# Even.net
KiCad netlist of a schematic drawn in Altium Designer
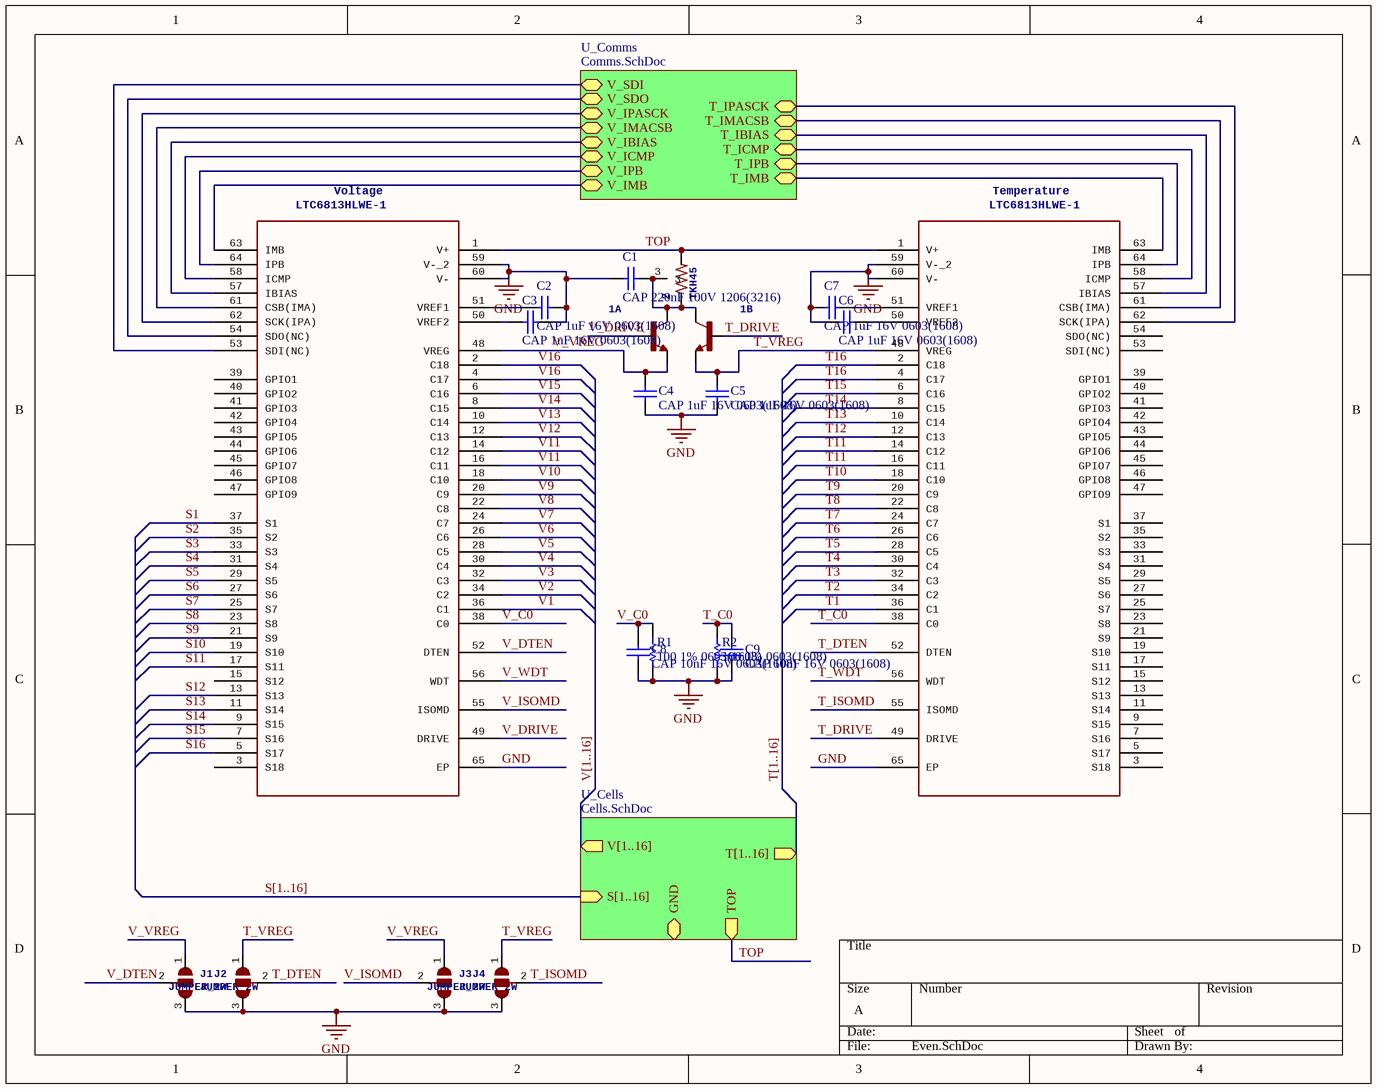
[diagram p0: Even.SchDoc]

(export (version "E")
  (design (tool "Eeschema 10.0.6"))
  (components
    (comp (ref "1")
      (value "PHPT610030NK")
      (footprint "LFPAK56D")
      (fields (field (name "LIBRARYNAME") "IFE_Transistors"))
      (libsource (lib "IFE_Transistors") (part "PHPT610030NK"))
    )
    (comp (ref "2")
      (value "TKH45")
      (footprint "TO252-TKH-45")
      (fields (field (name "LIBRARYNAME") "IFE_Resistors"))
      (libsource (lib "IFE_Resistors") (part "TKH45"))
    )
    (comp (ref "C1")
      (value "CAP 220nF 100V 1206(3216)")
      (footprint "CAPC1206(3216)190_L")
      (description "CAP 220nF 100V ±10% 1206 (3216 Metric) Thickness 1.9mm SMD")
      (fields (field (name "TOLERANCE") "Â±10%"))
      (libsource (lib "Altium Content Vault") (part "CAP"))
    )
    (comp (ref "C2")
      (value "CAP 1uF 16V 0603(1608)")
      (footprint "CAPC0603(1608)100_N")
      (description "CAP 1uF 16V ±5% 0603 (1608 Metric) Thickness 1mm SMD")
      (fields (field (name "TOLERANCE") "Â±5%"))
      (libsource (lib "Altium Content Vault") (part "CAP"))
    )
    (comp (ref "C3")
      (value "CAP 1uF 16V 0603(1608)")
      (footprint "CAPC0603(1608)100_N")
      (description "CAP 1uF 16V ±5% 0603 (1608 Metric) Thickness 1mm SMD")
      (fields (field (name "TOLERANCE") "Â±5%"))
      (libsource (lib "Altium Content Vault") (part "CAP"))
    )
    (comp (ref "C4")
      (value "CAP 1uF 16V 0603(1608)")
      (footprint "CAPC0603(1608)100_N")
      (description "CAP 1uF 16V ±5% 0603 (1608 Metric) Thickness 1mm SMD")
      (fields (field (name "TOLERANCE") "Â±5%"))
      (libsource (lib "Altium Content Vault") (part "CAP"))
    )
    (comp (ref "C5")
      (value "CAP 1uF 16V 0603(1608)")
      (footprint "CAPC0603(1608)100_N")
      (description "CAP 1uF 16V ±5% 0603 (1608 Metric) Thickness 1mm SMD")
      (fields (field (name "TOLERANCE") "Â±5%"))
      (libsource (lib "Altium Content Vault") (part "CAP"))
    )
    (comp (ref "C6")
      (value "CAP 1uF 16V 0603(1608)")
      (footprint "CAPC0603(1608)100_N")
      (description "CAP 1uF 16V ±5% 0603 (1608 Metric) Thickness 1mm SMD")
      (fields (field (name "TOLERANCE") "Â±5%"))
      (libsource (lib "Altium Content Vault") (part "CAP"))
    )
    (comp (ref "C7")
      (value "CAP 1uF 16V 0603(1608)")
      (footprint "CAPC0603(1608)100_N")
      (description "CAP 1uF 16V ±5% 0603 (1608 Metric) Thickness 1mm SMD")
      (fields (field (name "TOLERANCE") "Â±5%"))
      (libsource (lib "Altium Content Vault") (part "CAP"))
    )
    (comp (ref "C8")
      (value "CAP 10nF 16V 0603(1608)")
      (footprint "CAPC0603(1608)100_L")
      (description "CAP 10nF 16V ±1% 0603 (1608 Metric) Thickness 1mm SMD")
      (fields (field (name "TOLERANCE") "Â±1%"))
      (libsource (lib "Altium Content Vault") (part "CAP"))
    )
    (comp (ref "C9")
      (value "CAP 10nF 16V 0603(1608)")
      (footprint "CAPC0603(1608)100_L")
      (description "CAP 10nF 16V ±1% 0603 (1608 Metric) Thickness 1mm SMD")
      (fields (field (name "TOLERANCE") "Â±1%"))
      (libsource (lib "Altium Content Vault") (part "CAP"))
    )
    (comp (ref "J1")
      (value "JUMPER_2W")
      (footprint "SJ_2")
      (fields (field (name "LIBRARYNAME") "IFE_Jumpers"))
      (libsource (lib "") (part "JUMPER_2W_1"))
    )
    (comp (ref "J2")
      (value "JUMPER_2W")
      (footprint "SJ_2")
      (fields (field (name "LIBRARYNAME") "IFE_Jumpers"))
      (libsource (lib "IFE_Jumpers") (part "JUMPER_2W"))
    )
    (comp (ref "J3")
      (value "JUMPER_2W")
      (footprint "SJ_2")
      (fields (field (name "LIBRARYNAME") "IFE_Jumpers"))
      (libsource (lib "") (part "JUMPER_2W_1"))
    )
    (comp (ref "J4")
      (value "JUMPER_2W")
      (footprint "SJ_2")
      (fields (field (name "LIBRARYNAME") "IFE_Jumpers"))
      (libsource (lib "IFE_Jumpers") (part "JUMPER_2W"))
    )
    (comp (ref "R1")
      (value "100 1% 0603(1608)")
      (footprint "RESC0603(1608)_L")
      (description "2R94 0.1W 1% 0603 (1608 Metric)  SMD")
      (fields (field (name "POWER") "0.1 W") (field (name "TOLERANCE") "1 %"))
      (libsource (lib "Altium Content Vault") (part "RES"))
    )
    (comp (ref "R2")
      (value "100 1% 0603(1608)")
      (footprint "RESC0603(1608)_L")
      (description "2R94 0.1W 1% 0603 (1608 Metric)  SMD")
      (fields (field (name "POWER") "0.1 W") (field (name "TOLERANCE") "1 %"))
      (libsource (lib "Altium Content Vault") (part "RES"))
    )
    (comp (ref "Temperature")
      (value "LTC6813HLWE-1")
      (footprint "LQFP64_LWE_A")
      (fields (field (name "LIBRARYNAME") "LTC6813_Official"))
      (libsource (lib "LTC6813_Official") (part "LTC6813HLWE-1"))
    )
    (comp (ref "Voltage")
      (value "LTC6813HLWE-1")
      (footprint "LQFP64_LWE_A")
      (fields (field (name "LIBRARYNAME") "LTC6813_Official"))
      (libsource (lib "LTC6813_Official") (part "LTC6813HLWE-1"))
    )
  )
  (nets
    (net (code "2") (name "/S1") (class "Default")
      (node (ref "Voltage") (pin "37") (pinfunction "S1_37") (pintype "passive"))
    )
    (net (code "3") (name "/S2") (class "Default")
      (node (ref "Voltage") (pin "35") (pinfunction "S2_35") (pintype "passive"))
    )
    (net (code "4") (name "/S3") (class "Default")
      (node (ref "Voltage") (pin "33") (pinfunction "S3_33") (pintype "passive"))
    )
    (net (code "5") (name "/S4") (class "Default")
      (node (ref "Voltage") (pin "31") (pinfunction "S4_31") (pintype "passive"))
    )
    (net (code "6") (name "/S5") (class "Default")
      (node (ref "Voltage") (pin "29") (pinfunction "S5_29") (pintype "passive"))
    )
    (net (code "7") (name "/S6") (class "Default")
      (node (ref "Voltage") (pin "27") (pinfunction "S6_27") (pintype "passive"))
    )
    (net (code "8") (name "/S7") (class "Default")
      (node (ref "Voltage") (pin "25") (pinfunction "S7_25") (pintype "passive"))
    )
    (net (code "9") (name "/S8") (class "Default")
      (node (ref "Voltage") (pin "23") (pinfunction "S8_23") (pintype "passive"))
    )
    (net (code "10") (name "/S9") (class "Default")
      (node (ref "Voltage") (pin "21") (pinfunction "S9_21") (pintype "passive"))
    )
    (net (code "11") (name "/S10") (class "Default")
      (node (ref "Voltage") (pin "19") (pinfunction "S10_19") (pintype "passive"))
    )
    (net (code "12") (name "/S11") (class "Default")
      (node (ref "Voltage") (pin "17") (pinfunction "S11_17") (pintype "passive"))
    )
    (net (code "13") (name "/S12") (class "Default")
      (node (ref "Voltage") (pin "13") (pinfunction "S13_13") (pintype "passive"))
    )
    (net (code "14") (name "/S13") (class "Default")
      (node (ref "Voltage") (pin "11") (pinfunction "S14_11") (pintype "passive"))
    )
    (net (code "15") (name "/S14") (class "Default")
      (node (ref "Voltage") (pin "9") (pinfunction "S15_9") (pintype "passive"))
    )
    (net (code "16") (name "/S15") (class "Default")
      (node (ref "Voltage") (pin "7") (pinfunction "S16_7") (pintype "passive"))
    )
    (net (code "17") (name "/S16") (class "Default")
      (node (ref "Voltage") (pin "5") (pinfunction "S17_5") (pintype "passive"))
    )
    (net (code "19") (name "/T1") (class "Default")
      (node (ref "Temperature") (pin "36") (pinfunction "C1_36") (pintype "passive"))
    )
    (net (code "20") (name "/T2") (class "Default")
      (node (ref "Temperature") (pin "34") (pinfunction "C2_34") (pintype "passive"))
    )
    (net (code "21") (name "/T3") (class "Default")
      (node (ref "Temperature") (pin "32") (pinfunction "C3_32") (pintype "passive"))
    )
    (net (code "22") (name "/T4") (class "Default")
      (node (ref "Temperature") (pin "30") (pinfunction "C4_30") (pintype "passive"))
    )
    (net (code "23") (name "/T5") (class "Default")
      (node (ref "Temperature") (pin "28") (pinfunction "C5_28") (pintype "passive"))
    )
    (net (code "24") (name "/T6") (class "Default")
      (node (ref "Temperature") (pin "26") (pinfunction "C6_26") (pintype "passive"))
    )
    (net (code "25") (name "/T7") (class "Default")
      (node (ref "Temperature") (pin "24") (pinfunction "C7_24") (pintype "passive"))
    )
    (net (code "26") (name "/T8") (class "Default")
      (node (ref "Temperature") (pin "22") (pinfunction "C8_22") (pintype "passive"))
    )
    (net (code "27") (name "/T9") (class "Default")
      (node (ref "Temperature") (pin "20") (pinfunction "C9_20") (pintype "passive"))
    )
    (net (code "28") (name "/T10") (class "Default")
      (node (ref "Temperature") (pin "18") (pinfunction "C10_18") (pintype "passive"))
    )
    (net (code "29") (name "/T11") (class "Default")
      (node (ref "Temperature") (pin "14") (pinfunction "C12_14") (pintype "passive"))
      (node (ref "Temperature") (pin "16") (pinfunction "C11_16") (pintype "passive"))
    )
    (net (code "30") (name "/T12") (class "Default")
      (node (ref "Temperature") (pin "12") (pinfunction "C13_12") (pintype "passive"))
    )
    (net (code "31") (name "/T13") (class "Default")
      (node (ref "Temperature") (pin "10") (pinfunction "C14_10") (pintype "passive"))
    )
    (net (code "32") (name "/T14") (class "Default")
      (node (ref "Temperature") (pin "8") (pinfunction "C15_8") (pintype "passive"))
    )
    (net (code "33") (name "/T15") (class "Default")
      (node (ref "Temperature") (pin "6") (pinfunction "C16_6") (pintype "passive"))
    )
    (net (code "34") (name "/T16") (class "Default")
      (node (ref "Temperature") (pin "2") (pinfunction "C18_2") (pintype "passive"))
      (node (ref "Temperature") (pin "4") (pinfunction "C17_4") (pintype "passive"))
    )
    (net (code "35") (name "/TOP") (class "Default")
      (node (ref "2") (pin "2") (pinfunction "2_2") (pintype "passive"))
      (node (ref "Temperature") (pin "1") (pinfunction "V+_1") (pintype "passive"))
      (node (ref "Voltage") (pin "1") (pinfunction "V+_1") (pintype "passive"))
    )
    (net (code "37") (name "/T_C0") (class "Default")
      (node (ref "C9") (pin "2") (pinfunction "2_2") (pintype "passive"))
      (node (ref "R2") (pin "1") (pinfunction "1_1") (pintype "passive"))
      (node (ref "Temperature") (pin "38") (pinfunction "C0_38") (pintype "passive"))
    )
    (net (code "38") (name "/T_DRIVE") (class "Default")
      (node (ref "1") (pin "B2") (pinfunction "B_B2") (pintype "passive"))
      (node (ref "Temperature") (pin "49") (pinfunction "DRIVE_49") (pintype "passive"))
    )
    (net (code "39") (name "/T_DTEN") (class "Default")
      (node (ref "J2") (pin "2") (pinfunction "2_2") (pintype "passive"))
      (node (ref "Temperature") (pin "52") (pinfunction "DTEN_52") (pintype "passive"))
    )
    (net (code "40") (name "/T_IBIAS") (class "Default")
      (node (ref "Temperature") (pin "57") (pinfunction "IBIAS_57") (pintype "passive"))
    )
    (net (code "41") (name "/T_ICMP") (class "Default")
      (node (ref "Temperature") (pin "58") (pinfunction "ICMP_58") (pintype "passive"))
    )
    (net (code "42") (name "/T_IMACSB") (class "Default")
      (node (ref "Temperature") (pin "61") (pinfunction "CSB(IMA)_61") (pintype "passive"))
    )
    (net (code "43") (name "/T_IMB") (class "Default")
      (node (ref "Temperature") (pin "63") (pinfunction "IMB_63") (pintype "passive"))
    )
    (net (code "44") (name "/T_IPASCK") (class "Default")
      (node (ref "Temperature") (pin "62") (pinfunction "SCK(IPA)_62") (pintype "passive"))
    )
    (net (code "45") (name "/T_IPB") (class "Default")
      (node (ref "Temperature") (pin "64") (pinfunction "IPB_64") (pintype "passive"))
    )
    (net (code "46") (name "/T_ISOMD") (class "Default")
      (node (ref "J4") (pin "2") (pinfunction "2_2") (pintype "passive"))
      (node (ref "Temperature") (pin "55") (pinfunction "ISOMD_55") (pintype "passive"))
    )
    (net (code "47") (name "/T_VREG") (class "Default")
      (node (ref "1") (pin "E2") (pinfunction "E_E2") (pintype "passive"))
      (node (ref "C5") (pin "2") (pinfunction "2_2") (pintype "passive"))
      (node (ref "J2") (pin "1") (pinfunction "1_1") (pintype "passive"))
      (node (ref "J4") (pin "1") (pinfunction "1_1") (pintype "passive"))
      (node (ref "Temperature") (pin "48") (pinfunction "VREG_48") (pintype "passive"))
    )
    (net (code "48") (name "/T_WDT") (class "Default")
      (node (ref "Temperature") (pin "56") (pinfunction "WDT_56") (pintype "passive"))
    )
    (net (code "49") (name "/V1") (class "Default")
      (node (ref "Voltage") (pin "36") (pinfunction "C1_36") (pintype "passive"))
    )
    (net (code "50") (name "/V2") (class "Default")
      (node (ref "Voltage") (pin "34") (pinfunction "C2_34") (pintype "passive"))
    )
    (net (code "51") (name "/V3") (class "Default")
      (node (ref "Voltage") (pin "32") (pinfunction "C3_32") (pintype "passive"))
    )
    (net (code "52") (name "/V4") (class "Default")
      (node (ref "Voltage") (pin "30") (pinfunction "C4_30") (pintype "passive"))
    )
    (net (code "53") (name "/V5") (class "Default")
      (node (ref "Voltage") (pin "28") (pinfunction "C5_28") (pintype "passive"))
    )
    (net (code "54") (name "/V6") (class "Default")
      (node (ref "Voltage") (pin "26") (pinfunction "C6_26") (pintype "passive"))
    )
    (net (code "55") (name "/V7") (class "Default")
      (node (ref "Voltage") (pin "24") (pinfunction "C7_24") (pintype "passive"))
    )
    (net (code "56") (name "/V8") (class "Default")
      (node (ref "Voltage") (pin "22") (pinfunction "C8_22") (pintype "passive"))
    )
    (net (code "57") (name "/V9") (class "Default")
      (node (ref "Voltage") (pin "20") (pinfunction "C9_20") (pintype "passive"))
    )
    (net (code "58") (name "/V10") (class "Default")
      (node (ref "Voltage") (pin "18") (pinfunction "C10_18") (pintype "passive"))
    )
    (net (code "59") (name "/V11") (class "Default")
      (node (ref "Voltage") (pin "14") (pinfunction "C12_14") (pintype "passive"))
      (node (ref "Voltage") (pin "16") (pinfunction "C11_16") (pintype "passive"))
    )
    (net (code "60") (name "/V12") (class "Default")
      (node (ref "Voltage") (pin "12") (pinfunction "C13_12") (pintype "passive"))
    )
    (net (code "61") (name "/V13") (class "Default")
      (node (ref "Voltage") (pin "10") (pinfunction "C14_10") (pintype "passive"))
    )
    (net (code "62") (name "/V14") (class "Default")
      (node (ref "Voltage") (pin "8") (pinfunction "C15_8") (pintype "passive"))
    )
    (net (code "63") (name "/V15") (class "Default")
      (node (ref "Voltage") (pin "6") (pinfunction "C16_6") (pintype "passive"))
    )
    (net (code "64") (name "/V16") (class "Default")
      (node (ref "Voltage") (pin "2") (pinfunction "C18_2") (pintype "passive"))
      (node (ref "Voltage") (pin "4") (pinfunction "C17_4") (pintype "passive"))
    )
    (net (code "66") (name "/V_C0") (class "Default")
      (node (ref "C8") (pin "1") (pinfunction "1_1") (pintype "passive"))
      (node (ref "R1") (pin "2") (pinfunction "2_2") (pintype "passive"))
      (node (ref "Voltage") (pin "38") (pinfunction "C0_38") (pintype "passive"))
    )
    (net (code "67") (name "/V_DRIVE") (class "Default")
      (node (ref "1") (pin "B1") (pinfunction "B_B1") (pintype "passive"))
      (node (ref "Voltage") (pin "49") (pinfunction "DRIVE_49") (pintype "passive"))
    )
    (net (code "68") (name "/V_DTEN") (class "Default")
      (node (ref "J1") (pin "2") (pinfunction "2_2") (pintype "passive"))
      (node (ref "Voltage") (pin "52") (pinfunction "DTEN_52") (pintype "passive"))
    )
    (net (code "69") (name "/V_IBIAS") (class "Default")
      (node (ref "Voltage") (pin "57") (pinfunction "IBIAS_57") (pintype "passive"))
    )
    (net (code "70") (name "/V_ICMP") (class "Default")
      (node (ref "Voltage") (pin "58") (pinfunction "ICMP_58") (pintype "passive"))
    )
    (net (code "71") (name "/V_IMACSB") (class "Default")
      (node (ref "Voltage") (pin "61") (pinfunction "CSB(IMA)_61") (pintype "passive"))
    )
    (net (code "72") (name "/V_IMB") (class "Default")
      (node (ref "Voltage") (pin "63") (pinfunction "IMB_63") (pintype "passive"))
    )
    (net (code "73") (name "/V_IPASCK") (class "Default")
      (node (ref "Voltage") (pin "62") (pinfunction "SCK(IPA)_62") (pintype "passive"))
    )
    (net (code "74") (name "/V_IPB") (class "Default")
      (node (ref "Voltage") (pin "64") (pinfunction "IPB_64") (pintype "passive"))
    )
    (net (code "75") (name "/V_ISOMD") (class "Default")
      (node (ref "J3") (pin "2") (pinfunction "2_2") (pintype "passive"))
      (node (ref "Voltage") (pin "55") (pinfunction "ISOMD_55") (pintype "passive"))
    )
    (net (code "76") (name "/V_SDI") (class "Default")
      (node (ref "Voltage") (pin "53") (pinfunction "SDI(NC)_53") (pintype "passive"))
    )
    (net (code "77") (name "/V_SDO") (class "Default")
      (node (ref "Voltage") (pin "54") (pinfunction "SDO(NC)_54") (pintype "passive"))
    )
    (net (code "78") (name "/V_VREG") (class "Default")
      (node (ref "1") (pin "E1") (pinfunction "E_E1") (pintype "passive"))
      (node (ref "C4") (pin "2") (pinfunction "2_2") (pintype "passive"))
      (node (ref "J1") (pin "1") (pinfunction "1_1") (pintype "passive"))
      (node (ref "J3") (pin "1") (pinfunction "1_1") (pintype "passive"))
      (node (ref "Voltage") (pin "48") (pinfunction "VREG_48") (pintype "passive"))
    )
    (net (code "79") (name "/V_WDT") (class "Default")
      (node (ref "Voltage") (pin "56") (pinfunction "WDT_56") (pintype "passive"))
    )
    (net (code "80") (name "GND") (class "Default")
      (node (ref "C1") (pin "1") (pinfunction "1_1") (pintype "passive"))
      (node (ref "C2") (pin "2") (pinfunction "2_2") (pintype "passive"))
      (node (ref "C3") (pin "2") (pinfunction "2_2") (pintype "passive"))
      (node (ref "C4") (pin "1") (pinfunction "1_1") (pintype "passive"))
      (node (ref "C5") (pin "1") (pinfunction "1_1") (pintype "passive"))
      (node (ref "C6") (pin "1") (pinfunction "1_1") (pintype "passive"))
      (node (ref "C7") (pin "1") (pinfunction "1_1") (pintype "passive"))
      (node (ref "C8") (pin "2") (pinfunction "2_2") (pintype "passive"))
      (node (ref "C9") (pin "1") (pinfunction "1_1") (pintype "passive"))
      (node (ref "J1") (pin "3") (pinfunction "3_3") (pintype "passive"))
      (node (ref "J2") (pin "3") (pinfunction "3_3") (pintype "passive"))
      (node (ref "J3") (pin "3") (pinfunction "3_3") (pintype "passive"))
      (node (ref "J4") (pin "3") (pinfunction "3_3") (pintype "passive"))
      (node (ref "R1") (pin "1") (pinfunction "1_1") (pintype "passive"))
      (node (ref "R2") (pin "2") (pinfunction "2_2") (pintype "passive"))
      (node (ref "Temperature") (pin "59") (pinfunction "V-_2_59") (pintype "passive"))
      (node (ref "Temperature") (pin "60") (pinfunction "V-_60") (pintype "passive"))
      (node (ref "Temperature") (pin "65") (pinfunction "EP_65") (pintype "passive"))
      (node (ref "Voltage") (pin "59") (pinfunction "V-_2_59") (pintype "passive"))
      (node (ref "Voltage") (pin "60") (pinfunction "V-_60") (pintype "passive"))
      (node (ref "Voltage") (pin "65") (pinfunction "EP_65") (pintype "passive"))
    )
    (net (code "81") (name "Net-(1A-C)") (class "Default")
      (node (ref "1") (pin "C1") (pinfunction "C_C1") (pintype "passive"))
      (node (ref "1") (pin "C2") (pinfunction "C_C2") (pintype "passive"))
      (node (ref "2") (pin "1") (pinfunction "1_1") (pintype "passive"))
      (node (ref "2") (pin "3") (pinfunction "3_3") (pintype "passive"))
      (node (ref "C1") (pin "2") (pinfunction "2_2") (pintype "passive"))
    )
    (net (code "82") (name "Net-(Temperature-VREF1)") (class "Default")
      (node (ref "C7") (pin "2") (pinfunction "2_2") (pintype "passive"))
      (node (ref "Temperature") (pin "51") (pinfunction "VREF1_51") (pintype "passive"))
    )
    (net (code "83") (name "Net-(Temperature-VREF2)") (class "Default")
      (node (ref "C6") (pin "2") (pinfunction "2_2") (pintype "passive"))
      (node (ref "Temperature") (pin "50") (pinfunction "VREF2_50") (pintype "passive"))
    )
    (net (code "84") (name "Net-(Voltage-VREF1)") (class "Default")
      (node (ref "C2") (pin "1") (pinfunction "1_1") (pintype "passive"))
      (node (ref "Voltage") (pin "51") (pinfunction "VREF1_51") (pintype "passive"))
    )
    (net (code "85") (name "Net-(Voltage-VREF2)") (class "Default")
      (node (ref "C3") (pin "1") (pinfunction "1_1") (pintype "passive"))
      (node (ref "Voltage") (pin "50") (pinfunction "VREF2_50") (pintype "passive"))
    )
    (net (code "86") (name "unconnected-(Temperature-GPIO1-Pad39)") (class "Default")
      (node (ref "Temperature") (pin "39") (pinfunction "GPIO1_39") (pintype "passive"))
    )
    (net (code "87") (name "unconnected-(Temperature-GPIO2-Pad40)") (class "Default")
      (node (ref "Temperature") (pin "40") (pinfunction "GPIO2_40") (pintype "passive"))
    )
    (net (code "88") (name "unconnected-(Temperature-GPIO3-Pad41)") (class "Default")
      (node (ref "Temperature") (pin "41") (pinfunction "GPIO3_41") (pintype "passive"))
    )
    (net (code "89") (name "unconnected-(Temperature-GPIO4-Pad42)") (class "Default")
      (node (ref "Temperature") (pin "42") (pinfunction "GPIO4_42") (pintype "passive"))
    )
    (net (code "90") (name "unconnected-(Temperature-GPIO5-Pad43)") (class "Default")
      (node (ref "Temperature") (pin "43") (pinfunction "GPIO5_43") (pintype "passive"))
    )
    (net (code "91") (name "unconnected-(Temperature-GPIO6-Pad44)") (class "Default")
      (node (ref "Temperature") (pin "44") (pinfunction "GPIO6_44") (pintype "passive"))
    )
    (net (code "92") (name "unconnected-(Temperature-GPIO7-Pad45)") (class "Default")
      (node (ref "Temperature") (pin "45") (pinfunction "GPIO7_45") (pintype "passive"))
    )
    (net (code "93") (name "unconnected-(Temperature-GPIO8-Pad46)") (class "Default")
      (node (ref "Temperature") (pin "46") (pinfunction "GPIO8_46") (pintype "passive"))
    )
    (net (code "94") (name "unconnected-(Temperature-GPIO9-Pad47)") (class "Default")
      (node (ref "Temperature") (pin "47") (pinfunction "GPIO9_47") (pintype "passive"))
    )
    (net (code "95") (name "unconnected-(Temperature-S1-Pad37)") (class "Default")
      (node (ref "Temperature") (pin "37") (pinfunction "S1_37") (pintype "passive"))
    )
    (net (code "96") (name "unconnected-(Temperature-S2-Pad35)") (class "Default")
      (node (ref "Temperature") (pin "35") (pinfunction "S2_35") (pintype "passive"))
    )
    (net (code "97") (name "unconnected-(Temperature-S3-Pad33)") (class "Default")
      (node (ref "Temperature") (pin "33") (pinfunction "S3_33") (pintype "passive"))
    )
    (net (code "98") (name "unconnected-(Temperature-S4-Pad31)") (class "Default")
      (node (ref "Temperature") (pin "31") (pinfunction "S4_31") (pintype "passive"))
    )
    (net (code "99") (name "unconnected-(Temperature-S5-Pad29)") (class "Default")
      (node (ref "Temperature") (pin "29") (pinfunction "S5_29") (pintype "passive"))
    )
    (net (code "100") (name "unconnected-(Temperature-S6-Pad27)") (class "Default")
      (node (ref "Temperature") (pin "27") (pinfunction "S6_27") (pintype "passive"))
    )
    (net (code "101") (name "unconnected-(Temperature-S7-Pad25)") (class "Default")
      (node (ref "Temperature") (pin "25") (pinfunction "S7_25") (pintype "passive"))
    )
    (net (code "102") (name "unconnected-(Temperature-S8-Pad23)") (class "Default")
      (node (ref "Temperature") (pin "23") (pinfunction "S8_23") (pintype "passive"))
    )
    (net (code "103") (name "unconnected-(Temperature-S9-Pad21)") (class "Default")
      (node (ref "Temperature") (pin "21") (pinfunction "S9_21") (pintype "passive"))
    )
    (net (code "104") (name "unconnected-(Temperature-S10-Pad19)") (class "Default")
      (node (ref "Temperature") (pin "19") (pinfunction "S10_19") (pintype "passive"))
    )
    (net (code "105") (name "unconnected-(Temperature-S11-Pad17)") (class "Default")
      (node (ref "Temperature") (pin "17") (pinfunction "S11_17") (pintype "passive"))
    )
    (net (code "106") (name "unconnected-(Temperature-S12-Pad15)") (class "Default")
      (node (ref "Temperature") (pin "15") (pinfunction "S12_15") (pintype "passive"))
    )
    (net (code "107") (name "unconnected-(Temperature-S13-Pad13)") (class "Default")
      (node (ref "Temperature") (pin "13") (pinfunction "S13_13") (pintype "passive"))
    )
    (net (code "108") (name "unconnected-(Temperature-S14-Pad11)") (class "Default")
      (node (ref "Temperature") (pin "11") (pinfunction "S14_11") (pintype "passive"))
    )
    (net (code "109") (name "unconnected-(Temperature-S15-Pad9)") (class "Default")
      (node (ref "Temperature") (pin "9") (pinfunction "S15_9") (pintype "passive"))
    )
    (net (code "110") (name "unconnected-(Temperature-S16-Pad7)") (class "Default")
      (node (ref "Temperature") (pin "7") (pinfunction "S16_7") (pintype "passive"))
    )
    (net (code "111") (name "unconnected-(Temperature-S17-Pad5)") (class "Default")
      (node (ref "Temperature") (pin "5") (pinfunction "S17_5") (pintype "passive"))
    )
    (net (code "112") (name "unconnected-(Temperature-S18-Pad3)") (class "Default")
      (node (ref "Temperature") (pin "3") (pinfunction "S18_3") (pintype "passive"))
    )
    (net (code "113") (name "unconnected-(Temperature-SDI(NC)-Pad53)") (class "Default")
      (node (ref "Temperature") (pin "53") (pinfunction "SDI(NC)_53") (pintype "passive"))
    )
    (net (code "114") (name "unconnected-(Temperature-SDO(NC)-Pad54)") (class "Default")
      (node (ref "Temperature") (pin "54") (pinfunction "SDO(NC)_54") (pintype "passive"))
    )
    (net (code "115") (name "unconnected-(Voltage-GPIO1-Pad39)") (class "Default")
      (node (ref "Voltage") (pin "39") (pinfunction "GPIO1_39") (pintype "passive"))
    )
    (net (code "116") (name "unconnected-(Voltage-GPIO2-Pad40)") (class "Default")
      (node (ref "Voltage") (pin "40") (pinfunction "GPIO2_40") (pintype "passive"))
    )
    (net (code "117") (name "unconnected-(Voltage-GPIO3-Pad41)") (class "Default")
      (node (ref "Voltage") (pin "41") (pinfunction "GPIO3_41") (pintype "passive"))
    )
    (net (code "118") (name "unconnected-(Voltage-GPIO4-Pad42)") (class "Default")
      (node (ref "Voltage") (pin "42") (pinfunction "GPIO4_42") (pintype "passive"))
    )
    (net (code "119") (name "unconnected-(Voltage-GPIO5-Pad43)") (class "Default")
      (node (ref "Voltage") (pin "43") (pinfunction "GPIO5_43") (pintype "passive"))
    )
    (net (code "120") (name "unconnected-(Voltage-GPIO6-Pad44)") (class "Default")
      (node (ref "Voltage") (pin "44") (pinfunction "GPIO6_44") (pintype "passive"))
    )
    (net (code "121") (name "unconnected-(Voltage-GPIO7-Pad45)") (class "Default")
      (node (ref "Voltage") (pin "45") (pinfunction "GPIO7_45") (pintype "passive"))
    )
    (net (code "122") (name "unconnected-(Voltage-GPIO8-Pad46)") (class "Default")
      (node (ref "Voltage") (pin "46") (pinfunction "GPIO8_46") (pintype "passive"))
    )
    (net (code "123") (name "unconnected-(Voltage-GPIO9-Pad47)") (class "Default")
      (node (ref "Voltage") (pin "47") (pinfunction "GPIO9_47") (pintype "passive"))
    )
    (net (code "124") (name "unconnected-(Voltage-S12-Pad15)") (class "Default")
      (node (ref "Voltage") (pin "15") (pinfunction "S12_15") (pintype "passive"))
    )
    (net (code "125") (name "unconnected-(Voltage-S18-Pad3)") (class "Default")
      (node (ref "Voltage") (pin "3") (pinfunction "S18_3") (pintype "passive"))
    )
  )
)
